# rotator_interface.net
KiCad netlist of a schematic drawn in EAGLE
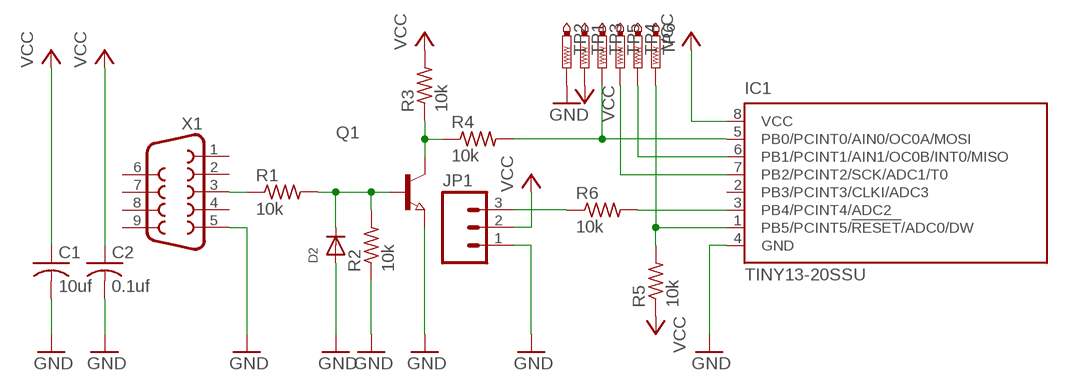
[diagram p0: schematic, sheet 1]

(export (version "E")
  (design (tool "Eeschema 10.0.6"))
  (components
    (comp (ref "C1")
      (value "10uf")
      (footprint "eagle-import:C1206")
      (libsource (lib "eagle-import") (part "C-USC1206"))
    )
    (comp (ref "C2")
      (value "0.1uf")
      (footprint "eagle-import:C1206")
      (libsource (lib "eagle-import") (part "C-USC1206"))
    )
    (comp (ref "D2")
      (value "DIODESOD-123")
      (footprint "eagle-import:SOD-123")
      (libsource (lib "eagle-import") (part "DIODESOD-123"))
    )
    (comp (ref "IC1")
      (value "TINY13-20SSU")
      (footprint "eagle-import:8S1")
      (fields (field (name "MPN") "ATTINY13-20SSU"))
      (libsource (lib "eagle-import") (part "TINY13SSU-20"))
    )
    (comp (ref "JP1")
      (value "M03PTH")
      (footprint "eagle-import:1X03")
      (libsource (lib "eagle-import") (part "M03PTH"))
    )
    (comp (ref "Q1")
      (value "NPN-TRANSISTOR_SOT23")
      (footprint "eagle-import:SOT23")
      (libsource (lib "eagle-import") (part "NPN-TRANSISTOR_SOT23"))
    )
    (comp (ref "R1")
      (value "10k")
      (footprint "eagle-import:R1206")
      (libsource (lib "eagle-import") (part "R-US_R1206"))
    )
    (comp (ref "R2")
      (value "10k")
      (footprint "eagle-import:R1206")
      (libsource (lib "eagle-import") (part "R-US_R1206"))
    )
    (comp (ref "R3")
      (value "10k")
      (footprint "eagle-import:R1206")
      (libsource (lib "eagle-import") (part "R-US_R1206"))
    )
    (comp (ref "R4")
      (value "10k")
      (footprint "eagle-import:R1206")
      (libsource (lib "eagle-import") (part "R-US_R1206"))
    )
    (comp (ref "R5")
      (value "10k")
      (footprint "eagle-import:R1206")
      (libsource (lib "eagle-import") (part "R-US_R1206"))
    )
    (comp (ref "R6")
      (value "10k")
      (footprint "eagle-import:R1206")
      (libsource (lib "eagle-import") (part "R-US_R1206"))
    )
    (comp (ref "TP1")
      (value "PTR1B1,27")
      (footprint "eagle-import:B1,27")
      (libsource (lib "eagle-import") (part "PTR1B1,27"))
    )
    (comp (ref "TP2")
      (value "PTR1B1,27")
      (footprint "eagle-import:B1,27")
      (libsource (lib "eagle-import") (part "PTR1B1,27"))
    )
    (comp (ref "TP3")
      (value "PTR1B1,27")
      (footprint "eagle-import:B1,27")
      (libsource (lib "eagle-import") (part "PTR1B1,27"))
    )
    (comp (ref "TP4")
      (value "PTR1B1,27")
      (footprint "eagle-import:B1,27")
      (libsource (lib "eagle-import") (part "PTR1B1,27"))
    )
    (comp (ref "TP5")
      (value "PTR1B1,27")
      (footprint "eagle-import:B1,27")
      (libsource (lib "eagle-import") (part "PTR1B1,27"))
    )
    (comp (ref "TP6")
      (value "PTR1B1,27")
      (footprint "eagle-import:B1,27")
      (libsource (lib "eagle-import") (part "PTR1B1,27"))
    )
    (comp (ref "X1")
      (value "DB9FEMALE")
      (footprint "eagle-import:DB9")
      (libsource (lib "eagle-import") (part "DB9FEMALE"))
    )
  )
  (nets
    (net (code "1") (name "GND") (class "Default")
      (node (ref "C1") (pin "2") (pinfunction "2_2") (pintype "passive"))
      (node (ref "C2") (pin "2") (pinfunction "2_2") (pintype "passive"))
      (node (ref "D2") (pin "A") (pinfunction "A_A") (pintype "passive"))
      (node (ref "IC1") (pin "4") (pinfunction "GND_4") (pintype "power_in"))
      (node (ref "JP1") (pin "1") (pinfunction "1_1") (pintype "passive"))
      (node (ref "Q1") (pin "2") (pinfunction "E_2") (pintype "passive"))
      (node (ref "R2") (pin "1") (pinfunction "1_1") (pintype "passive"))
      (node (ref "TP2") (pin "TP") (pinfunction "TP_TP") (pintype "input"))
      (node (ref "X1") (pin "5") (pinfunction "5_5") (pintype "passive"))
    )
    (net (code "2") (name "Net-(IC1-PB0{slash}PCINT0{slash}AIN0{slash}OC0A{slash}MOSI)") (class "Default")
      (node (ref "IC1") (pin "5") (pinfunction "PB0/PCINT0/AIN0/OC0A/MOSI_5") (pintype "bidirectional"))
      (node (ref "R4") (pin "2") (pinfunction "2_2") (pintype "passive"))
      (node (ref "TP3") (pin "TP") (pinfunction "TP_TP") (pintype "input"))
    )
    (net (code "3") (name "Net-(IC1-PB1{slash}PCINT1{slash}AIN1{slash}OC0B{slash}INT0{slash}MISO)") (class "Default")
      (node (ref "IC1") (pin "6") (pinfunction "PB1/PCINT1/AIN1/OC0B/INT0/MISO_6") (pintype "bidirectional"))
      (node (ref "TP4") (pin "TP") (pinfunction "TP_TP") (pintype "input"))
    )
    (net (code "4") (name "Net-(IC1-PB2{slash}PCINT2{slash}SCK{slash}ADC1{slash}T0)") (class "Default")
      (node (ref "IC1") (pin "7") (pinfunction "PB2/PCINT2/SCK/ADC1/T0_7") (pintype "bidirectional"))
      (node (ref "TP5") (pin "TP") (pinfunction "TP_TP") (pintype "input"))
    )
    (net (code "5") (name "Net-(IC1-PB4{slash}PCINT4{slash}ADC2)") (class "Default")
      (node (ref "IC1") (pin "3") (pinfunction "PB4/PCINT4/ADC2_3") (pintype "bidirectional"))
      (node (ref "R6") (pin "2") (pinfunction "2_2") (pintype "passive"))
    )
    (net (code "6") (name "Net-(IC1-PB5{slash}PCINT5{slash}~{RESET}{slash}ADC0{slash}DW)") (class "Default")
      (node (ref "IC1") (pin "1") (pinfunction "PB5/PCINT5/~{RESET}/ADC0/DW_1") (pintype "bidirectional"))
      (node (ref "R5") (pin "2") (pinfunction "2_2") (pintype "passive"))
      (node (ref "TP6") (pin "TP") (pinfunction "TP_TP") (pintype "input"))
    )
    (net (code "7") (name "Net-(JP1-Pad3)") (class "Default")
      (node (ref "JP1") (pin "3") (pinfunction "3_3") (pintype "passive"))
      (node (ref "R6") (pin "1") (pinfunction "1_1") (pintype "passive"))
    )
    (net (code "8") (name "Net-(Q1-B)") (class "Default")
      (node (ref "D2") (pin "C") (pinfunction "C_C") (pintype "passive"))
      (node (ref "Q1") (pin "1") (pinfunction "B_1") (pintype "passive"))
      (node (ref "R1") (pin "2") (pinfunction "2_2") (pintype "passive"))
      (node (ref "R2") (pin "2") (pinfunction "2_2") (pintype "passive"))
    )
    (net (code "9") (name "Net-(Q1-C)") (class "Default")
      (node (ref "Q1") (pin "3") (pinfunction "C_3") (pintype "passive"))
      (node (ref "R3") (pin "1") (pinfunction "1_1") (pintype "passive"))
      (node (ref "R4") (pin "1") (pinfunction "1_1") (pintype "passive"))
    )
    (net (code "10") (name "Net-(R1-Pad1)") (class "Default")
      (node (ref "R1") (pin "1") (pinfunction "1_1") (pintype "passive"))
      (node (ref "X1") (pin "3") (pinfunction "3_3") (pintype "passive"))
    )
    (net (code "11") (name "VCC") (class "Default")
      (node (ref "C1") (pin "1") (pinfunction "1_1") (pintype "passive"))
      (node (ref "C2") (pin "1") (pinfunction "1_1") (pintype "passive"))
      (node (ref "IC1") (pin "8") (pinfunction "VCC_8") (pintype "power_in"))
      (node (ref "JP1") (pin "2") (pinfunction "2_2") (pintype "passive"))
      (node (ref "R3") (pin "2") (pinfunction "2_2") (pintype "passive"))
      (node (ref "R5") (pin "1") (pinfunction "1_1") (pintype "passive"))
      (node (ref "TP1") (pin "TP") (pinfunction "TP_TP") (pintype "input"))
    )
    (net (code "12") (name "unconnected-(IC1-PB3{slash}PCINT3{slash}CLKI{slash}ADC3-Pad2)") (class "Default")
      (node (ref "IC1") (pin "2") (pinfunction "PB3/PCINT3/CLKI/ADC3_2") (pintype "bidirectional"))
    )
    (net (code "13") (name "unconnected-(X1-Pad1)") (class "Default")
      (node (ref "X1") (pin "1") (pinfunction "1_1") (pintype "passive"))
    )
    (net (code "14") (name "unconnected-(X1-Pad2)") (class "Default")
      (node (ref "X1") (pin "2") (pinfunction "2_2") (pintype "passive"))
    )
    (net (code "15") (name "unconnected-(X1-Pad4)") (class "Default")
      (node (ref "X1") (pin "4") (pinfunction "4_4") (pintype "passive"))
    )
    (net (code "16") (name "unconnected-(X1-Pad6)") (class "Default")
      (node (ref "X1") (pin "6") (pinfunction "6_6") (pintype "passive"))
    )
    (net (code "17") (name "unconnected-(X1-Pad7)") (class "Default")
      (node (ref "X1") (pin "7") (pinfunction "7_7") (pintype "passive"))
    )
    (net (code "18") (name "unconnected-(X1-Pad8)") (class "Default")
      (node (ref "X1") (pin "8") (pinfunction "8_8") (pintype "passive"))
    )
    (net (code "19") (name "unconnected-(X1-Pad9)") (class "Default")
      (node (ref "X1") (pin "9") (pinfunction "9_9") (pintype "passive"))
    )
  )
)
